# meltdown_interface.net
KiCad netlist of a schematic drawn in Altium Designer
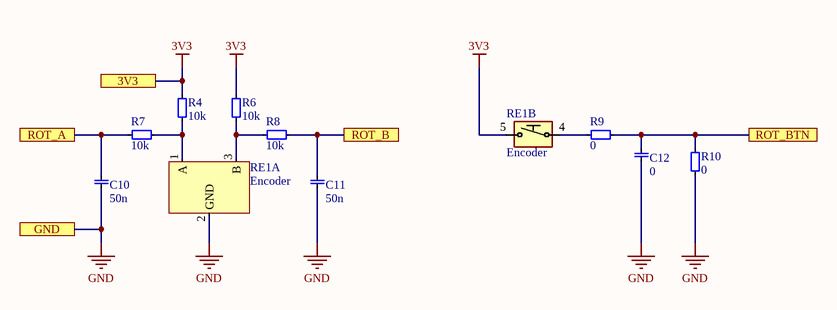
[diagram p0: meltdown_interface.SchDoc]

(export (version "E")
  (design (tool "Eeschema 10.0.6"))
  (components
    (comp (ref "C10")
      (value "50n")
      (footprint "0603 cap")
      (fields (field (name "Comment") "0603, capacitor"))
      (libsource (lib "jclib") (part "0603, capacitor"))
    )
    (comp (ref "C11")
      (value "50n")
      (footprint "0603 cap")
      (fields (field (name "Comment") "0603, capacitor"))
      (libsource (lib "jclib") (part "0603, capacitor"))
    )
    (comp (ref "C12")
      (value "0")
      (footprint "0603 cap")
      (fields (field (name "Comment") "0603, capacitor"))
      (libsource (lib "jclib") (part "0603, capacitor"))
    )
    (comp (ref "R4")
      (value "10k")
      (footprint "0603")
      (fields (field (name "Comment") "0603, resistor"))
      (libsource (lib "jclib") (part "0603, resistor"))
    )
    (comp (ref "R6")
      (value "10k")
      (footprint "0603")
      (fields (field (name "Comment") "0603, resistor"))
      (libsource (lib "jclib") (part "0603, resistor"))
    )
    (comp (ref "R7")
      (value "10k")
      (footprint "0603")
      (fields (field (name "Comment") "0603, resistor"))
      (libsource (lib "jclib") (part "0603, resistor"))
    )
    (comp (ref "R8")
      (value "10k")
      (footprint "0603")
      (fields (field (name "Comment") "0603, resistor"))
      (libsource (lib "jclib") (part "0603, resistor"))
    )
    (comp (ref "R9")
      (value "0")
      (footprint "0603")
      (fields (field (name "Comment") "0603, resistor"))
      (libsource (lib "jclib") (part "0603, resistor"))
    )
    (comp (ref "R10")
      (value "0")
      (footprint "0603")
      (fields (field (name "Comment") "0603, resistor"))
      (libsource (lib "jclib") (part "0603, resistor"))
    )
    (comp (ref "RE1")
      (value "Encoder")
      (footprint "RotaryEncoder")
      (libsource (lib "jclib") (part "Rotary Encoder with Button"))
    )
  )
  (nets
    (net (code "1") (name "/ROT_A") (class "Default")
      (node (ref "C10") (pin "1") (pinfunction "1_1") (pintype "passive"))
      (node (ref "R7") (pin "0") (pinfunction "0_0") (pintype "passive"))
    )
    (net (code "2") (name "/ROT_B") (class "Default")
      (node (ref "C11") (pin "1") (pinfunction "1_1") (pintype "passive"))
      (node (ref "R8") (pin "0") (pinfunction "0_0") (pintype "passive"))
    )
    (net (code "3") (name "/ROT_BTN") (class "Default")
      (node (ref "C12") (pin "1") (pinfunction "1_1") (pintype "passive"))
      (node (ref "R10") (pin "0") (pinfunction "0_0") (pintype "passive"))
      (node (ref "R9") (pin "1") (pinfunction "1_1") (pintype "passive"))
    )
    (net (code "4") (name "3V3") (class "Default")
      (node (ref "R4") (pin "0") (pinfunction "0_0") (pintype "passive"))
      (node (ref "R6") (pin "0") (pinfunction "0_0") (pintype "passive"))
      (node (ref "RE1") (pin "5") (pinfunction "B_5") (pintype "passive"))
    )
    (net (code "5") (name "GND") (class "Default")
      (node (ref "C10") (pin "0") (pinfunction "0_0") (pintype "passive"))
      (node (ref "C11") (pin "0") (pinfunction "0_0") (pintype "passive"))
      (node (ref "C12") (pin "0") (pinfunction "0_0") (pintype "passive"))
      (node (ref "R10") (pin "1") (pinfunction "1_1") (pintype "passive"))
      (node (ref "RE1") (pin "2") (pinfunction "GND_2") (pintype "passive"))
    )
    (net (code "6") (name "Net-(R9-Pad0)") (class "Default")
      (node (ref "R9") (pin "0") (pinfunction "0_0") (pintype "passive"))
      (node (ref "RE1") (pin "4") (pinfunction "B_4") (pintype "passive"))
    )
    (net (code "7") (name "Net-(RE1A-A)") (class "Default")
      (node (ref "R4") (pin "1") (pinfunction "1_1") (pintype "passive"))
      (node (ref "R7") (pin "1") (pinfunction "1_1") (pintype "passive"))
      (node (ref "RE1") (pin "1") (pinfunction "A_1") (pintype "passive"))
    )
    (net (code "8") (name "Net-(RE1A-B)") (class "Default")
      (node (ref "R6") (pin "1") (pinfunction "1_1") (pintype "passive"))
      (node (ref "R8") (pin "1") (pinfunction "1_1") (pintype "passive"))
      (node (ref "RE1") (pin "3") (pinfunction "B_3") (pintype "passive"))
    )
  )
)
